# 06_SAMA7G54-MPU.net
KiCad netlist of a schematic drawn in Altium Designer
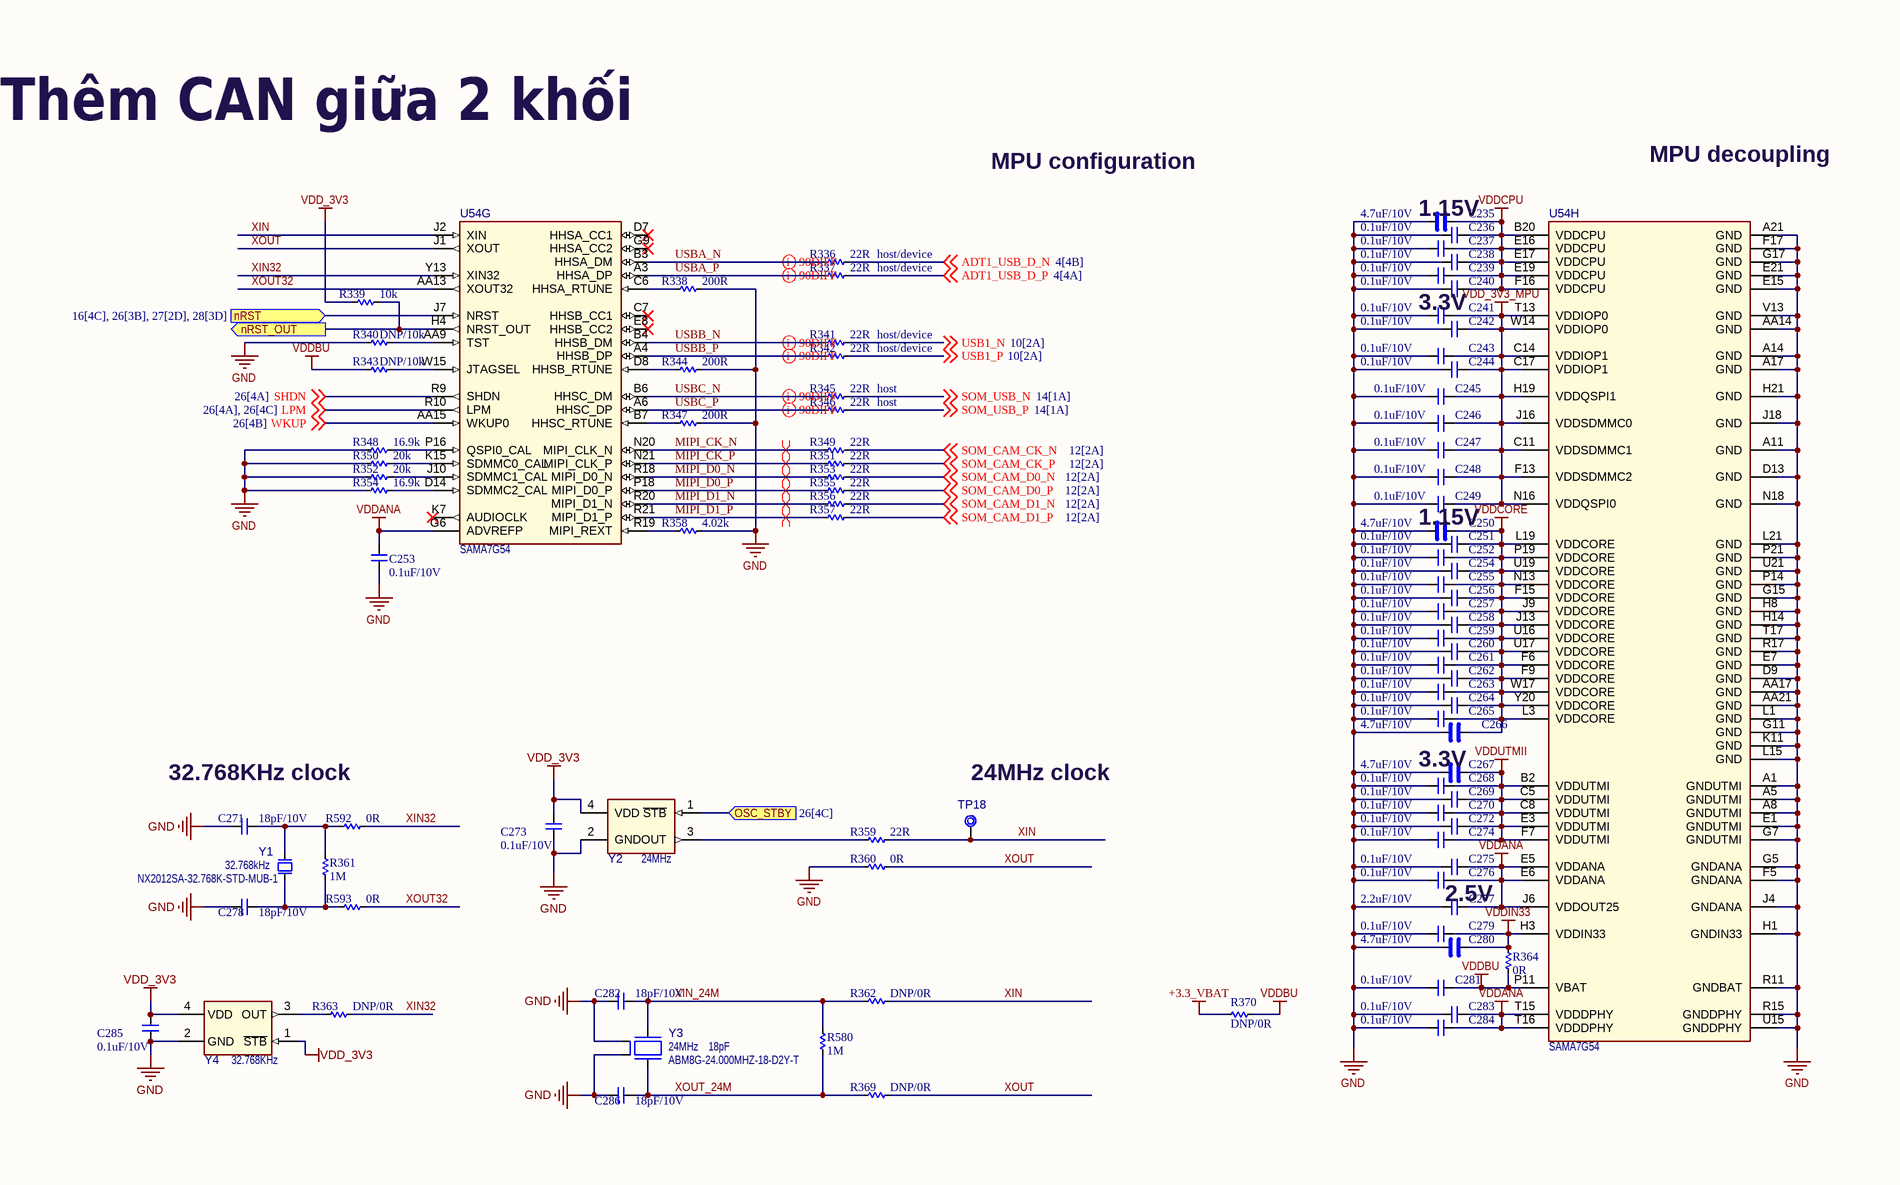
[diagram p0: 06_SAMA7G54-MPU.SchDoc, top left]
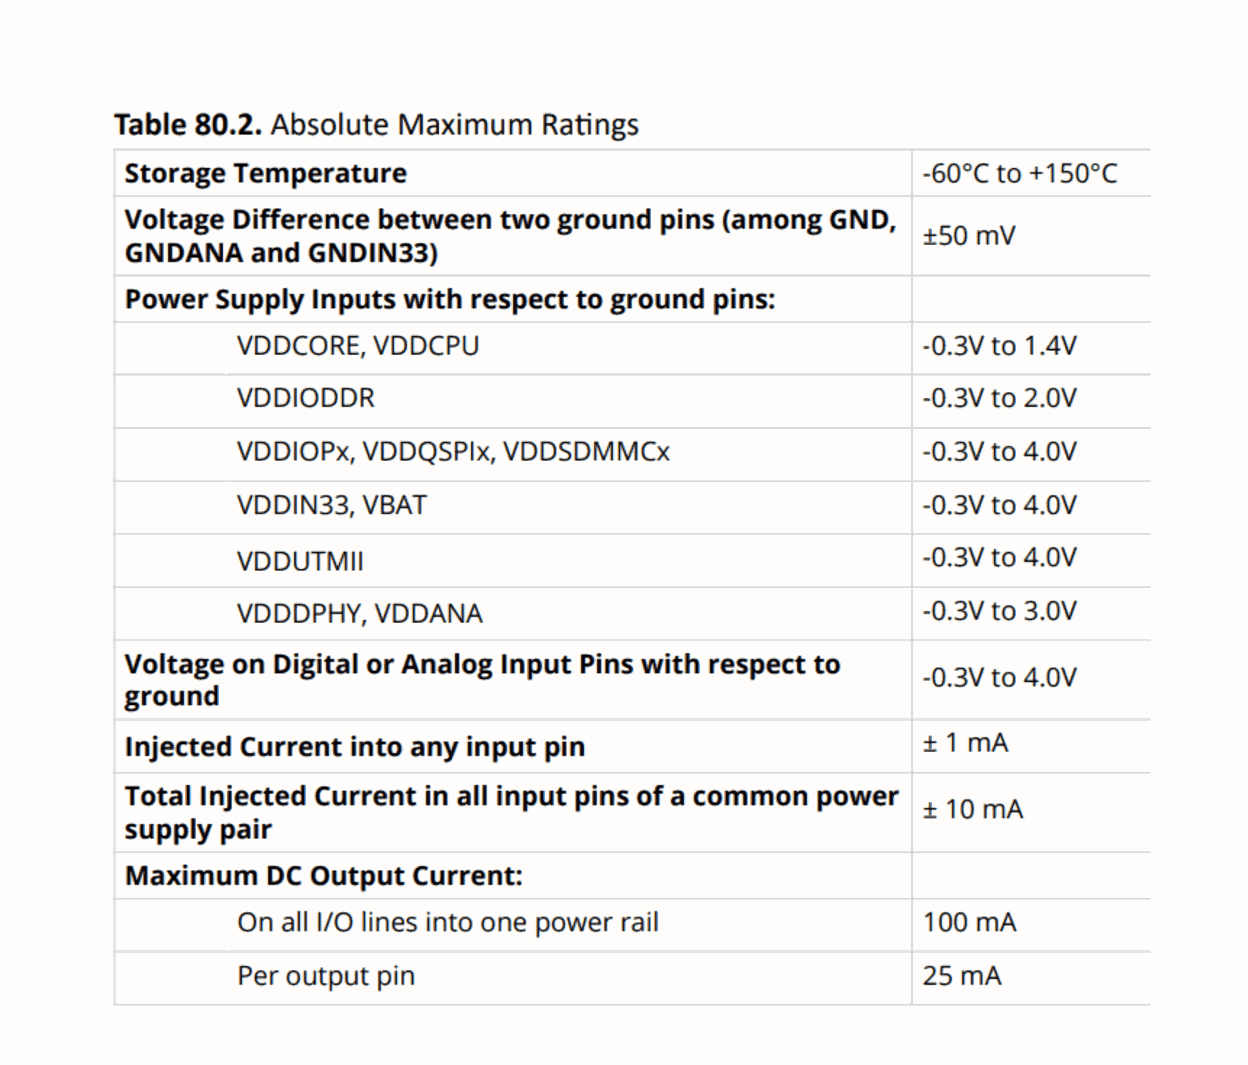
[diagram p1: 06_SAMA7G54-MPU.SchDoc, top right]
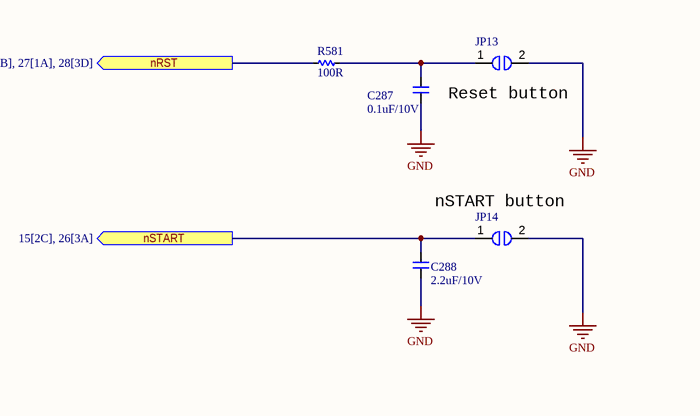
[diagram p2: 06_SAMA7G54-MPU.SchDoc, bottom left]
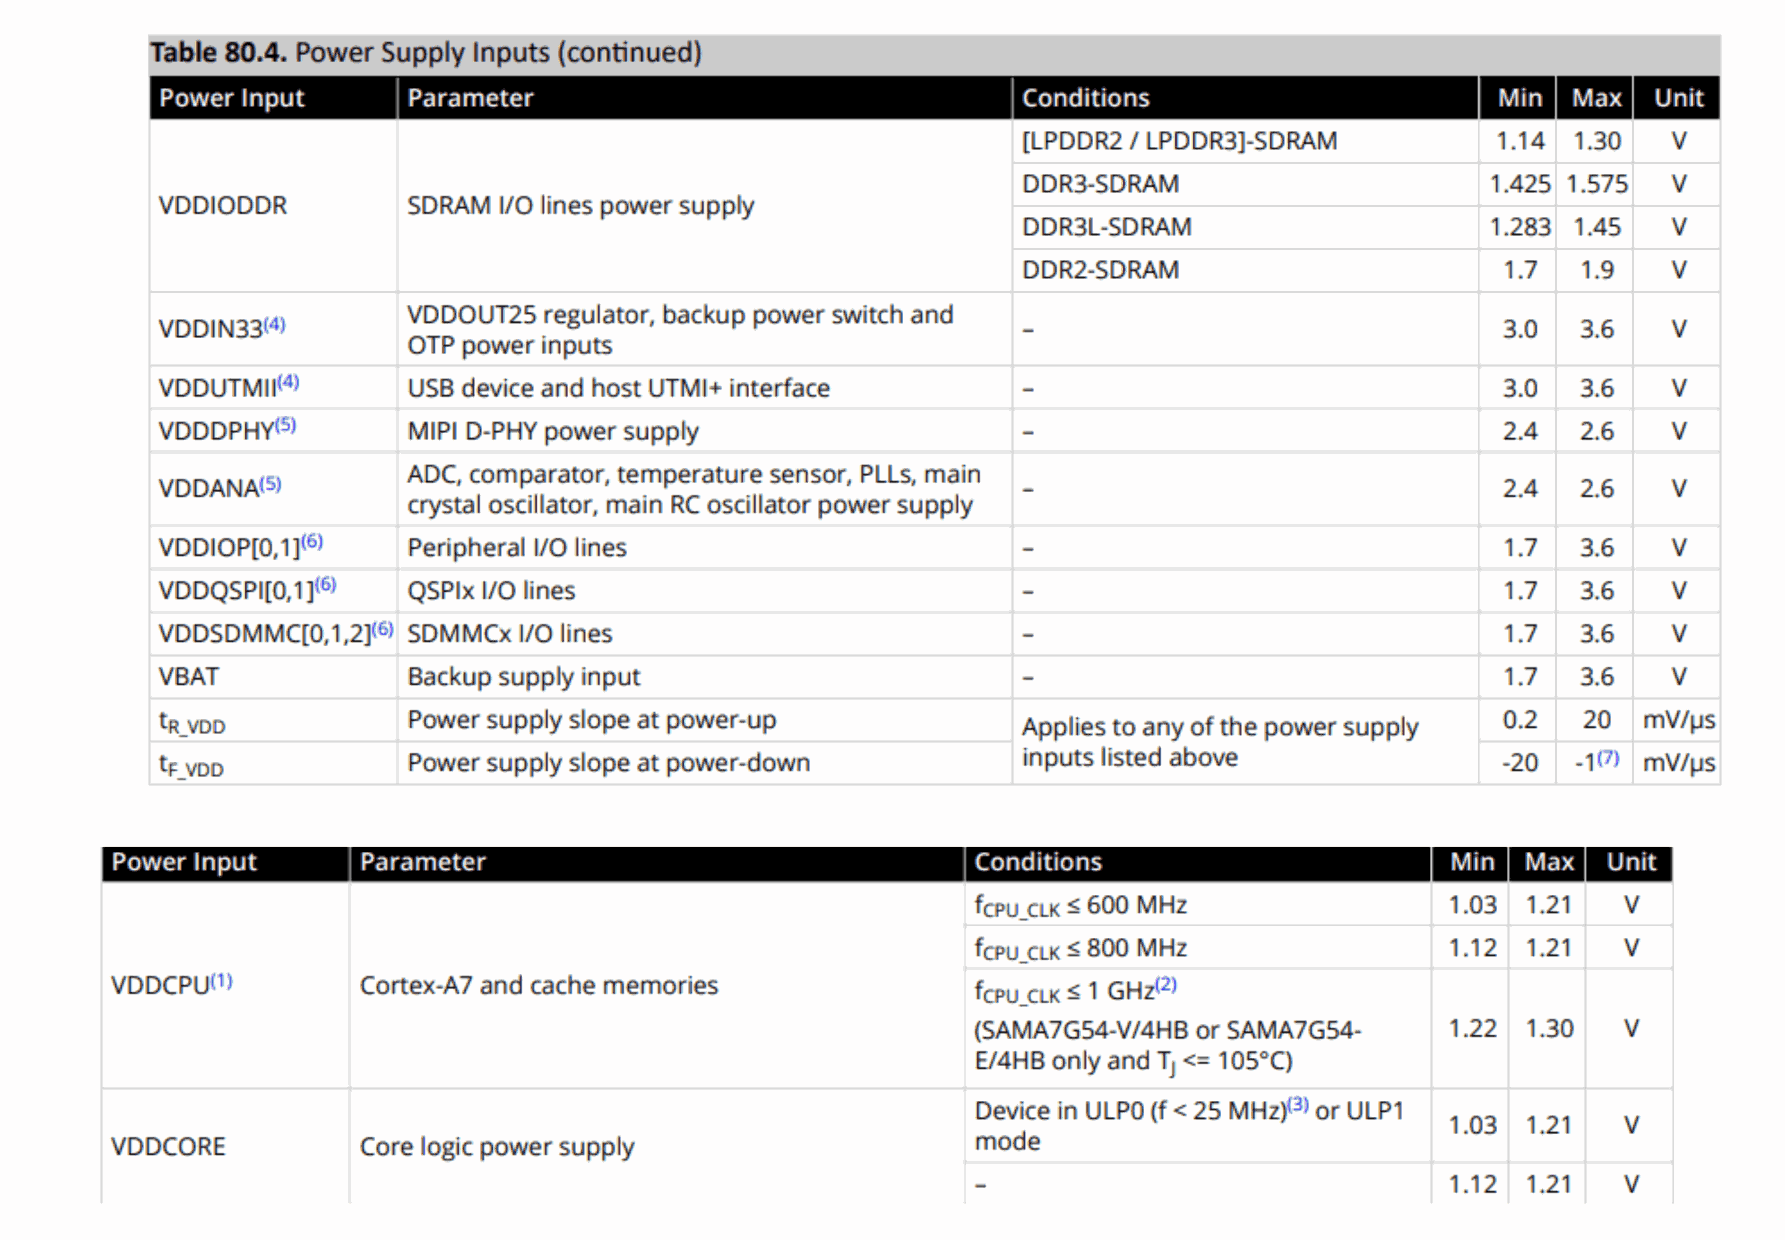
[diagram p3: 06_SAMA7G54-MPU.SchDoc, bottom right]

(export (version "E")
  (design (tool "Eeschema 10.0.6"))
  (components
    (comp (ref "C235")
      (value "4.7uF/10V")
      (footprint "CAP_C_1005X60")
      (description "CAP CHIP High Value")
      (libsource (lib "LABLIB") (part "_CAP_C_High_2"))
    )
    (comp (ref "C236")
      (value "0.1uF/10V")
      (footprint "CAP_C_0603x30")
      (description "CAP CHIP")
      (libsource (lib "LABLIB") (part "_CAP_C_2"))
    )
    (comp (ref "C237")
      (value "0.1uF/10V")
      (footprint "CAP_C_0603x30")
      (description "CAP CHIP")
      (libsource (lib "LABLIB") (part "_CAP_C_2"))
    )
    (comp (ref "C238")
      (value "0.1uF/10V")
      (footprint "CAP_C_0603x30")
      (description "CAP CHIP")
      (libsource (lib "LABLIB") (part "_CAP_C_2"))
    )
    (comp (ref "C239")
      (value "0.1uF/10V")
      (footprint "CAP_C_0603x30")
      (description "CAP CHIP")
      (libsource (lib "LABLIB") (part "_CAP_C_2"))
    )
    (comp (ref "C240")
      (value "0.1uF/10V")
      (footprint "CAP_C_0603x30")
      (description "CAP CHIP")
      (libsource (lib "LABLIB") (part "_CAP_C_2"))
    )
    (comp (ref "C241")
      (value "0.1uF/10V")
      (footprint "CAP_C_0603x30")
      (description "CAP CHIP")
      (libsource (lib "LABLIB") (part "_CAP_C_2"))
    )
    (comp (ref "C242")
      (value "0.1uF/10V")
      (footprint "CAP_C_0603x30")
      (description "CAP CHIP")
      (libsource (lib "LABLIB") (part "_CAP_C_2"))
    )
    (comp (ref "C243")
      (value "0.1uF/10V")
      (footprint "CAP_C_0603x30")
      (description "CAP CHIP")
      (libsource (lib "LABLIB") (part "_CAP_C_2"))
    )
    (comp (ref "C244")
      (value "0.1uF/10V")
      (footprint "CAP_C_0603x30")
      (description "CAP CHIP")
      (libsource (lib "LABLIB") (part "_CAP_C_2"))
    )
    (comp (ref "C245")
      (value "0.1uF/10V")
      (footprint "CAP_C_0603x30")
      (description "CAP CHIP")
      (libsource (lib "LABLIB") (part "_CAP_C_2"))
    )
    (comp (ref "C246")
      (value "0.1uF/10V")
      (footprint "CAP_C_0603x30")
      (description "CAP CHIP")
      (libsource (lib "LABLIB") (part "_CAP_C_2"))
    )
    (comp (ref "C247")
      (value "0.1uF/10V")
      (footprint "CAP_C_0603x30")
      (description "CAP CHIP")
      (libsource (lib "LABLIB") (part "_CAP_C_2"))
    )
    (comp (ref "C248")
      (value "0.1uF/10V")
      (footprint "CAP_C_0603x30")
      (description "CAP CHIP")
      (libsource (lib "LABLIB") (part "_CAP_C_2"))
    )
    (comp (ref "C249")
      (value "0.1uF/10V")
      (footprint "CAP_C_0603x30")
      (description "CAP CHIP")
      (libsource (lib "LABLIB") (part "_CAP_C_2"))
    )
    (comp (ref "C250")
      (value "4.7uF/10V")
      (footprint "CAP_C_1005X60")
      (description "CAP CHIP High Value")
      (libsource (lib "LABLIB") (part "_CAP_C_High_2"))
    )
    (comp (ref "C251")
      (value "0.1uF/10V")
      (footprint "CAP_C_0603x30")
      (description "CAP CHIP")
      (libsource (lib "LABLIB") (part "_CAP_C_2"))
    )
    (comp (ref "C252")
      (value "0.1uF/10V")
      (footprint "CAP_C_0603x30")
      (description "CAP CHIP")
      (libsource (lib "LABLIB") (part "_CAP_C_2"))
    )
    (comp (ref "C253")
      (value "0.1uF/10V")
      (footprint "CAP_C_0603x30")
      (description "CAP CHIP")
      (libsource (lib "LABLIB") (part "_CAP_C_2"))
    )
    (comp (ref "C254")
      (value "0.1uF/10V")
      (footprint "CAP_C_0603x30")
      (description "CAP CHIP")
      (libsource (lib "LABLIB") (part "_CAP_C_2"))
    )
    (comp (ref "C255")
      (value "0.1uF/10V")
      (footprint "CAP_C_0603x30")
      (description "CAP CHIP")
      (libsource (lib "LABLIB") (part "_CAP_C_2"))
    )
    (comp (ref "C256")
      (value "0.1uF/10V")
      (footprint "CAP_C_0603x30")
      (description "CAP CHIP")
      (libsource (lib "LABLIB") (part "_CAP_C_2"))
    )
    (comp (ref "C257")
      (value "0.1uF/10V")
      (footprint "CAP_C_0603x30")
      (description "CAP CHIP")
      (libsource (lib "LABLIB") (part "_CAP_C_2"))
    )
    (comp (ref "C258")
      (value "0.1uF/10V")
      (footprint "CAP_C_0603x30")
      (description "CAP CHIP")
      (libsource (lib "LABLIB") (part "_CAP_C_2"))
    )
    (comp (ref "C259")
      (value "0.1uF/10V")
      (footprint "CAP_C_0603x30")
      (description "CAP CHIP")
      (libsource (lib "LABLIB") (part "_CAP_C_2"))
    )
    (comp (ref "C260")
      (value "0.1uF/10V")
      (footprint "CAP_C_0603x30")
      (description "CAP CHIP")
      (libsource (lib "LABLIB") (part "_CAP_C_2"))
    )
    (comp (ref "C261")
      (value "0.1uF/10V")
      (footprint "CAP_C_0603x30")
      (description "CAP CHIP")
      (libsource (lib "LABLIB") (part "_CAP_C_2"))
    )
    (comp (ref "C262")
      (value "0.1uF/10V")
      (footprint "CAP_C_0603x30")
      (description "CAP CHIP")
      (libsource (lib "LABLIB") (part "_CAP_C_2"))
    )
    (comp (ref "C263")
      (value "0.1uF/10V")
      (footprint "CAP_C_0603x30")
      (description "CAP CHIP")
      (libsource (lib "LABLIB") (part "_CAP_C_2"))
    )
    (comp (ref "C264")
      (value "0.1uF/10V")
      (footprint "CAP_C_0603x30")
      (description "CAP CHIP")
      (libsource (lib "LABLIB") (part "_CAP_C_2"))
    )
    (comp (ref "C265")
      (value "0.1uF/10V")
      (footprint "CAP_C_0603x30")
      (description "CAP CHIP")
      (libsource (lib "LABLIB") (part "_CAP_C_2"))
    )
    (comp (ref "C266")
      (value "4.7uF/10V")
      (footprint "CAP_C_1005X60")
      (description "CAP CHIP High Value")
      (libsource (lib "LABLIB") (part "_CAP_C_High_2"))
    )
    (comp (ref "C267")
      (value "4.7uF/10V")
      (footprint "CAP_C_1005X60")
      (description "CAP CHIP High Value")
      (libsource (lib "LABLIB") (part "_CAP_C_High_2"))
    )
    (comp (ref "C268")
      (value "0.1uF/10V")
      (footprint "CAP_C_0603x30")
      (description "CAP CHIP")
      (libsource (lib "LABLIB") (part "_CAP_C_2"))
    )
    (comp (ref "C269")
      (value "0.1uF/10V")
      (footprint "CAP_C_0603x30")
      (description "CAP CHIP")
      (libsource (lib "LABLIB") (part "_CAP_C_2"))
    )
    (comp (ref "C270")
      (value "0.1uF/10V")
      (footprint "CAP_C_0603x30")
      (description "CAP CHIP")
      (libsource (lib "LABLIB") (part "_CAP_C_2"))
    )
    (comp (ref "C271")
      (value "18pF/10V")
      (footprint "CAP_C_1005X60")
      (description "CAP CHIP")
      (libsource (lib "LABLIB") (part "_CAP_C_2"))
    )
    (comp (ref "C272")
      (value "0.1uF/10V")
      (footprint "CAP_C_0603x30")
      (description "CAP CHIP")
      (libsource (lib "LABLIB") (part "_CAP_C_2"))
    )
    (comp (ref "C273")
      (value "0.1uF/10V")
      (footprint "CAP_C_1005X60")
      (description "CAP CHIP")
      (libsource (lib "LABLIB") (part "_CAP_C_2"))
    )
    (comp (ref "C274")
      (value "0.1uF/10V")
      (footprint "CAP_C_0603x30")
      (description "CAP CHIP")
      (libsource (lib "LABLIB") (part "_CAP_C_2"))
    )
    (comp (ref "C275")
      (value "0.1uF/10V")
      (footprint "CAP_C_0603x30")
      (description "CAP CHIP")
      (libsource (lib "LABLIB") (part "_CAP_C_2"))
    )
    (comp (ref "C276")
      (value "0.1uF/10V")
      (footprint "CAP_C_0603x30")
      (description "CAP CHIP")
      (libsource (lib "LABLIB") (part "_CAP_C_2"))
    )
    (comp (ref "C277")
      (value "2.2uF/10V")
      (footprint "CAP_C_1005X50_L")
      (description "CAP CHIP")
      (libsource (lib "LABLIB") (part "_CAP_C_2"))
    )
    (comp (ref "C278")
      (value "18pF/10V")
      (footprint "CAP_C_1005X60")
      (description "CAP CHIP")
      (libsource (lib "LABLIB") (part "_CAP_C_2"))
    )
    (comp (ref "C279")
      (value "0.1uF/10V")
      (footprint "CAP_C_0603x30")
      (description "CAP CHIP")
      (libsource (lib "LABLIB") (part "_CAP_C_2"))
    )
    (comp (ref "C280")
      (value "4.7uF/10V")
      (footprint "CAP_C_1005X60")
      (description "CAP CHIP High Value")
      (libsource (lib "LABLIB") (part "_CAP_C_High_2"))
    )
    (comp (ref "C281")
      (value "0.1uF/10V")
      (footprint "CAP_C_0603x30")
      (description "CAP CHIP")
      (libsource (lib "LABLIB") (part "_CAP_C_2"))
    )
    (comp (ref "C282")
      (value "18pF/10V")
      (footprint "CAP_C_1005X60")
      (description "CAP CHIP")
      (libsource (lib "LABLIB") (part "_CAP_C_2"))
    )
    (comp (ref "C283")
      (value "0.1uF/10V")
      (footprint "CAP_C_0603x30")
      (description "CAP CHIP")
      (libsource (lib "LABLIB") (part "_CAP_C_2"))
    )
    (comp (ref "C284")
      (value "0.1uF/10V")
      (footprint "CAP_C_0603x30")
      (description "CAP CHIP")
      (libsource (lib "LABLIB") (part "_CAP_C_2"))
    )
    (comp (ref "C285")
      (value "0.1uF/10V")
      (footprint "CAP_C_1005X60")
      (description "CAP CHIP")
      (libsource (lib "LABLIB") (part "_CAP_C_2"))
    )
    (comp (ref "C286")
      (value "18pF/10V")
      (footprint "CAP_C_1005X60")
      (description "CAP CHIP")
      (libsource (lib "LABLIB") (part "_CAP_C_2"))
    )
    (comp (ref "C287")
      (value "0.1uF/10V")
      (footprint "CAP_C_1005X60")
      (description "CAP CHIP")
      (libsource (lib "LABLIB") (part "_CAP_C_2"))
    )
    (comp (ref "C288")
      (value "2.2uF/10V")
      (footprint "CAP_C_1005X50_L")
      (description "CAP CHIP")
      (libsource (lib "LABLIB") (part "_CAP_C_2"))
    )
    (comp (ref "JP13")
      (value "~")
      (footprint "TESTPOINT_SHORT_120X100_60")
      (libsource (lib "LABLIB") (part "JUMPER_1_1"))
    )
    (comp (ref "JP14")
      (value "~")
      (footprint "TESTPOINT_SHORT_120X100_60")
      (libsource (lib "LABLIB") (part "JUMPER_1_1"))
    )
    (comp (ref "R336")
      (value "22R")
      (footprint "RES_C_0603X30")
      (description "RES")
      (libsource (lib "LABLIB") (part "_RES_B_2"))
    )
    (comp (ref "R337")
      (value "22R")
      (footprint "RES_C_0603X30")
      (description "RES")
      (libsource (lib "LABLIB") (part "_RES_B_2"))
    )
    (comp (ref "R338")
      (value "200R")
      (footprint "RES_C_0603X30")
      (description "RES")
      (libsource (lib "LABLIB") (part "_RES_B_2"))
    )
    (comp (ref "R339")
      (value "10k")
      (footprint "RES_C_1005X40")
      (description "RES")
      (libsource (lib "LABLIB") (part "_RES_B_2"))
    )
    (comp (ref "R340")
      (value "DNP/10k")
      (footprint "RES_C_1005X40")
      (description "RES")
      (libsource (lib "LABLIB") (part "_RES_B_2"))
    )
    (comp (ref "R341")
      (value "22R")
      (footprint "RES_C_0603X30")
      (description "RES")
      (libsource (lib "LABLIB") (part "_RES_B_2"))
    )
    (comp (ref "R342")
      (value "22R")
      (footprint "RES_C_0603X30")
      (description "RES")
      (libsource (lib "LABLIB") (part "_RES_B_2"))
    )
    (comp (ref "R343")
      (value "DNP/10k")
      (footprint "RES_C_1005X40")
      (description "RES")
      (libsource (lib "LABLIB") (part "_RES_B_2"))
    )
    (comp (ref "R344")
      (value "200R")
      (footprint "RES_C_0603X30")
      (description "RES")
      (libsource (lib "LABLIB") (part "_RES_B_2"))
    )
    (comp (ref "R345")
      (value "22R")
      (footprint "RES_C_0603X30")
      (description "RES")
      (libsource (lib "LABLIB") (part "_RES_B_2"))
    )
    (comp (ref "R346")
      (value "22R")
      (footprint "RES_C_0603X30")
      (description "RES")
      (libsource (lib "LABLIB") (part "_RES_B_2"))
    )
    (comp (ref "R347")
      (value "200R")
      (footprint "RES_C_0603X30")
      (description "RES")
      (libsource (lib "LABLIB") (part "_RES_B_2"))
    )
    (comp (ref "R348")
      (value "16.9k")
      (footprint "RES_C_0603X30")
      (description "RES")
      (libsource (lib "LABLIB") (part "_RES_B_2"))
    )
    (comp (ref "R349")
      (value "22R")
      (footprint "RES_C_0603X30")
      (description "RES")
      (libsource (lib "LABLIB") (part "_RES_B_2"))
    )
    (comp (ref "R350")
      (value "20k")
      (footprint "RES_C_0603X30")
      (description "RES")
      (libsource (lib "LABLIB") (part "_RES_B_2"))
    )
    (comp (ref "R351")
      (value "22R")
      (footprint "RES_C_0603X30")
      (description "RES")
      (libsource (lib "LABLIB") (part "_RES_B_2"))
    )
    (comp (ref "R352")
      (value "20k")
      (footprint "RES_C_0603X30")
      (description "RES")
      (libsource (lib "LABLIB") (part "_RES_B_2"))
    )
    (comp (ref "R353")
      (value "22R")
      (footprint "RES_C_0603X30")
      (description "RES")
      (libsource (lib "LABLIB") (part "_RES_B_2"))
    )
    (comp (ref "R354")
      (value "16.9k")
      (footprint "RES_C_0603X30")
      (description "RES")
      (libsource (lib "LABLIB") (part "_RES_B_2"))
    )
    (comp (ref "R355")
      (value "22R")
      (footprint "RES_C_0603X30")
      (description "RES")
      (libsource (lib "LABLIB") (part "_RES_B_2"))
    )
    (comp (ref "R356")
      (value "22R")
      (footprint "RES_C_0603X30")
      (description "RES")
      (libsource (lib "LABLIB") (part "_RES_B_2"))
    )
    (comp (ref "R357")
      (value "22R")
      (footprint "RES_C_0603X30")
      (description "RES")
      (libsource (lib "LABLIB") (part "_RES_B_2"))
    )
    (comp (ref "R358")
      (value "4.02k")
      (footprint "RES_C_0603X30")
      (description "RES")
      (libsource (lib "LABLIB") (part "_RES_B_2"))
    )
    (comp (ref "R359")
      (value "22R")
      (footprint "RES_C_1005X40")
      (description "RES")
      (libsource (lib "LABLIB") (part "_RES_B_2"))
    )
    (comp (ref "R360")
      (value "0R")
      (footprint "RES_C_1005X40")
      (description "RES")
      (libsource (lib "LABLIB") (part "_RES_B_2"))
    )
    (comp (ref "R361")
      (value "1M")
      (footprint "RES_C_1005X40")
      (description "RES")
      (libsource (lib "LABLIB") (part "_RES_B_2"))
    )
    (comp (ref "R362")
      (value "DNP/0R")
      (footprint "RES_C_1005X40")
      (description "RES")
      (libsource (lib "LABLIB") (part "_RES_B_2"))
    )
    (comp (ref "R363")
      (value "DNP/0R")
      (footprint "RES_C_1005X40")
      (description "RES")
      (libsource (lib "LABLIB") (part "_RES_B_2"))
    )
    (comp (ref "R364")
      (value "0R")
      (footprint "RES_C_1005X40")
      (description "RES")
      (libsource (lib "LABLIB") (part "_RES_B_2"))
    )
    (comp (ref "R369")
      (value "DNP/0R")
      (footprint "RES_C_1005X40")
      (description "RES")
      (libsource (lib "LABLIB") (part "_RES_B_2"))
    )
    (comp (ref "R370")
      (value "DNP/0R")
      (footprint "RES_C_1005X40")
      (description "RES")
      (libsource (lib "LABLIB") (part "_RES_B_2"))
    )
    (comp (ref "R580")
      (value "1M")
      (footprint "RES_C_1005X40")
      (description "RES")
      (libsource (lib "LABLIB") (part "_RES_B_2"))
    )
    (comp (ref "R581")
      (value "100R")
      (footprint "RES_C_1005X40")
      (description "RES")
      (libsource (lib "LABLIB") (part "_RES_B_2"))
    )
    (comp (ref "R592")
      (value "0R")
      (footprint "RES_C_1005X40")
      (description "RES")
      (libsource (lib "LABLIB") (part "_RES_B_2"))
    )
    (comp (ref "R593")
      (value "0R")
      (footprint "RES_C_1005X40")
      (description "RES")
      (libsource (lib "LABLIB") (part "_RES_B_2"))
    )
    (comp (ref "TP18")
      (value "Test Point No BOM")
      (footprint "Testpoint_80")
      (description "Test Point")
      (fields (field (name "OWNER") "Cristian Papuc"))
      (libsource (lib "MCHP-CDB") (part "Test Point No BOM"))
    )
    (comp (ref "U54")
      (value "SAMA7G54")
      (footprint "TFBGA-343_14x14")
      (description "SAMA7G54 MPU 1000MHz Cortex-A7 TFBGA-343")
      (fields (field (name "OWNER") "Ciprian Abramov"))
      (libsource (lib "MCHP-CDB") (part "SAMA7G54 TFBGA-343"))
    )
    (comp (ref "Y1")
      (value "32.768kHz")
      (footprint "CRYSTAL_NX2012SA")
      (description "Crystal")
      (fields
        (field (name "TOLERANCE") "±20ppm")
        (field (name "MANUFACTURER PART NUMBER 1") "NX2012SA-32.768K-STD-MUB-1")
        (field (name "Comment") "Crystal 2 Pins")
        (field (name "OWNER") "Jamus Griego")
      )
      (libsource (lib "MCHP-CDB") (part "Crystal 2 Pins"))
    )
    (comp (ref "Y2")
      (value "24MHz")
      (footprint "DFN-4_2.5x2")
      (fields (field (name "Comment") "DSC10xx DFN-4") (field (name "OWNER") "Maurizio Gavardoni"))
      (libsource (lib "MCHP-CDB") (part "DSC10xx DFN-4"))
    )
    (comp (ref "Y3")
      (value "24MHz")
      (footprint "CRYSTAL_ABM8G")
      (description "Crystal")
      (fields
        (field (name "LOAD CAPACITANCE") "18pF")
        (field (name "MANUFACTURER PART NUMBER 1") "ABM8G-24.000MHZ-18-D2Y-T")
        (field (name "Comment") "Crystal 4 Pins")
        (field (name "OWNER") "Mark Loper")
      )
      (libsource (lib "MCHP-CDB") (part "Crystal 4 Pins"))
    )
    (comp (ref "Y4")
      (value "32.768KHz")
      (footprint "DFN-4_2x1.6")
      (fields (field (name "Comment") "DSC60xx DFN-4_LGA-4") (field (name "OWNER") "Ciprian Abramov"))
      (libsource (lib "MCHP-CDB") (part "DSC60xx DFN-4_LGA-4"))
    )
  )
  (nets
    (net (code "1") (name "+3.3_VBAT") (class "Default")
      (node (ref "R370") (pin "1") (pinfunction "1_1") (pintype "passive"))
    )
    (net (code "2") (name "/MIPI_CK_N") (class "Default")
      (node (ref "R349") (pin "2") (pinfunction "2_2") (pintype "passive"))
      (node (ref "U54") (pin "N20") (pinfunction "MIPI_CLK_N_N20") (pintype "bidirectional"))
    )
    (net (code "3") (name "/MIPI_CK_P") (class "Default")
      (node (ref "R351") (pin "2") (pinfunction "2_2") (pintype "passive"))
      (node (ref "U54") (pin "N21") (pinfunction "MIPI_CLK_P_N21") (pintype "bidirectional"))
    )
    (net (code "4") (name "/MIPI_D0_N") (class "Default")
      (node (ref "R353") (pin "2") (pinfunction "2_2") (pintype "passive"))
      (node (ref "U54") (pin "R18") (pinfunction "MIPI_D0_N_R18") (pintype "bidirectional"))
    )
    (net (code "5") (name "/MIPI_D0_P") (class "Default")
      (node (ref "R355") (pin "2") (pinfunction "2_2") (pintype "passive"))
      (node (ref "U54") (pin "P18") (pinfunction "MIPI_D0_P_P18") (pintype "bidirectional"))
    )
    (net (code "6") (name "/MIPI_D1_N") (class "Default")
      (node (ref "R356") (pin "2") (pinfunction "2_2") (pintype "passive"))
      (node (ref "U54") (pin "R20") (pinfunction "MIPI_D1_N_R20") (pintype "bidirectional"))
    )
    (net (code "7") (name "/MIPI_D1_P") (class "Default")
      (node (ref "R357") (pin "2") (pinfunction "2_2") (pintype "passive"))
      (node (ref "U54") (pin "R21") (pinfunction "MIPI_D1_P_R21") (pintype "bidirectional"))
    )
    (net (code "8") (name "/OSC_STBY") (class "Default")
      (node (ref "Y2") (pin "1") (pinfunction "~{STB}_1") (pintype "input"))
    )
    (net (code "9") (name "/USBA_N") (class "Default")
      (node (ref "R336") (pin "2") (pinfunction "2_2") (pintype "passive"))
      (node (ref "U54") (pin "B3") (pinfunction "HHSA_DM_B3") (pintype "bidirectional"))
    )
    (net (code "10") (name "/USBA_P") (class "Default")
      (node (ref "R337") (pin "2") (pinfunction "2_2") (pintype "passive"))
      (node (ref "U54") (pin "A3") (pinfunction "HHSA_DP_A3") (pintype "bidirectional"))
    )
    (net (code "11") (name "/USBB_N") (class "Default")
      (node (ref "R341") (pin "2") (pinfunction "2_2") (pintype "passive"))
      (node (ref "U54") (pin "B4") (pinfunction "HHSB_DM_B4") (pintype "bidirectional"))
    )
    (net (code "12") (name "/USBB_P") (class "Default")
      (node (ref "R342") (pin "2") (pinfunction "2_2") (pintype "passive"))
      (node (ref "U54") (pin "A4") (pinfunction "HHSB_DP_A4") (pintype "bidirectional"))
    )
    (net (code "13") (name "/USBC_N") (class "Default")
      (node (ref "R345") (pin "2") (pinfunction "2_2") (pintype "passive"))
      (node (ref "U54") (pin "B6") (pinfunction "HHSC_DM_B6") (pintype "bidirectional"))
    )
    (net (code "14") (name "/USBC_P") (class "Default")
      (node (ref "R346") (pin "2") (pinfunction "2_2") (pintype "passive"))
      (node (ref "U54") (pin "A6") (pinfunction "HHSC_DP_A6") (pintype "bidirectional"))
    )
    (net (code "15") (name "/XIN") (class "Default")
      (node (ref "R359") (pin "2") (pinfunction "2_2") (pintype "passive"))
      (node (ref "R362") (pin "2") (pinfunction "2_2") (pintype "passive"))
      (node (ref "TP18") (pin "1") (pinfunction "1_1") (pintype "passive"))
      (node (ref "U54") (pin "J2") (pinfunction "XIN_J2") (pintype "input"))
    )
    (net (code "16") (name "/XIN32") (class "Default")
      (node (ref "R363") (pin "2") (pinfunction "2_2") (pintype "passive"))
      (node (ref "R592") (pin "2") (pinfunction "2_2") (pintype "passive"))
      (node (ref "U54") (pin "Y13") (pinfunction "XIN32_Y13") (pintype "input"))
    )
    (net (code "17") (name "/XIN_24M") (class "Default")
      (node (ref "C282") (pin "1") (pinfunction "1_1") (pintype "passive"))
      (node (ref "R362") (pin "1") (pinfunction "1_1") (pintype "passive"))
      (node (ref "R580") (pin "1") (pinfunction "1_1") (pintype "passive"))
      (node (ref "Y3") (pin "3") (pinfunction "Osc2_3") (pintype "passive"))
    )
    (net (code "18") (name "/XOUT") (class "Default")
      (node (ref "R360") (pin "2") (pinfunction "2_2") (pintype "passive"))
      (node (ref "R369") (pin "2") (pinfunction "2_2") (pintype "passive"))
      (node (ref "U54") (pin "J1") (pinfunction "XOUT_J1") (pintype "output"))
    )
    (net (code "19") (name "/XOUT32") (class "Default")
      (node (ref "R593") (pin "2") (pinfunction "2_2") (pintype "passive"))
      (node (ref "U54") (pin "AA13") (pinfunction "XOUT32_AA13") (pintype "output"))
    )
    (net (code "20") (name "/XOUT_24M") (class "Default")
      (node (ref "C286") (pin "1") (pinfunction "1_1") (pintype "passive"))
      (node (ref "R369") (pin "1") (pinfunction "1_1") (pintype "passive"))
      (node (ref "R580") (pin "2") (pinfunction "2_2") (pintype "passive"))
      (node (ref "Y3") (pin "1") (pinfunction "Osc1_1") (pintype "passive"))
    )
    (net (code "21") (name "/nRST") (class "Default")
      (node (ref "R581") (pin "1") (pinfunction "1_1") (pintype "passive"))
      (node (ref "U54") (pin "J7") (pinfunction "NRST_J7") (pintype "input"))
    )
    (net (code "22") (name "/nRST_OUT") (class "Default")
      (node (ref "R339") (pin "1") (pinfunction "1_1") (pintype "passive"))
      (node (ref "U54") (pin "H4") (pinfunction "NRST_OUT_H4") (pintype "output"))
    )
    (net (code "23") (name "/nSTART") (class "Default")
      (node (ref "C288") (pin "1") (pinfunction "1_1") (pintype "passive"))
      (node (ref "JP14") (pin "1") (pinfunction "1_1") (pintype "passive"))
    )
    (net (code "24") (name "ADT1_USB_D_N") (class "Default")
      (node (ref "R336") (pin "1") (pinfunction "1_1") (pintype "passive"))
    )
    (net (code "25") (name "ADT1_USB_D_P") (class "Default")
      (node (ref "R337") (pin "1") (pinfunction "1_1") (pintype "passive"))
    )
    (net (code "26") (name "GND") (class "Default")
      (node (ref "C235") (pin "2") (pinfunction "2_2") (pintype "passive"))
      (node (ref "C236") (pin "2") (pinfunction "2_2") (pintype "passive"))
      (node (ref "C237") (pin "2") (pinfunction "2_2") (pintype "passive"))
      (node (ref "C238") (pin "2") (pinfunction "2_2") (pintype "passive"))
      (node (ref "C239") (pin "2") (pinfunction "2_2") (pintype "passive"))
      (node (ref "C240") (pin "2") (pinfunction "2_2") (pintype "passive"))
      (node (ref "C241") (pin "2") (pinfunction "2_2") (pintype "passive"))
      (node (ref "C242") (pin "2") (pinfunction "2_2") (pintype "passive"))
      (node (ref "C243") (pin "2") (pinfunction "2_2") (pintype "passive"))
      (node (ref "C244") (pin "2") (pinfunction "2_2") (pintype "passive"))
      (node (ref "C245") (pin "2") (pinfunction "2_2") (pintype "passive"))
      (node (ref "C246") (pin "2") (pinfunction "2_2") (pintype "passive"))
      (node (ref "C247") (pin "2") (pinfunction "2_2") (pintype "passive"))
      (node (ref "C248") (pin "2") (pinfunction "2_2") (pintype "passive"))
      (node (ref "C249") (pin "2") (pinfunction "2_2") (pintype "passive"))
      (node (ref "C250") (pin "2") (pinfunction "2_2") (pintype "passive"))
      (node (ref "C251") (pin "2") (pinfunction "2_2") (pintype "passive"))
      (node (ref "C252") (pin "2") (pinfunction "2_2") (pintype "passive"))
      (node (ref "C253") (pin "1") (pinfunction "1_1") (pintype "passive"))
      (node (ref "C254") (pin "2") (pinfunction "2_2") (pintype "passive"))
      (node (ref "C255") (pin "2") (pinfunction "2_2") (pintype "passive"))
      (node (ref "C256") (pin "2") (pinfunction "2_2") (pintype "passive"))
      (node (ref "C257") (pin "2") (pinfunction "2_2") (pintype "passive"))
      (node (ref "C258") (pin "2") (pinfunction "2_2") (pintype "passive"))
      (node (ref "C259") (pin "2") (pinfunction "2_2") (pintype "passive"))
      (node (ref "C260") (pin "2") (pinfunction "2_2") (pintype "passive"))
      (node (ref "C261") (pin "2") (pinfunction "2_2") (pintype "passive"))
      (node (ref "C262") (pin "2") (pinfunction "2_2") (pintype "passive"))
      (node (ref "C263") (pin "2") (pinfunction "2_2") (pintype "passive"))
      (node (ref "C264") (pin "2") (pinfunction "2_2") (pintype "passive"))
      (node (ref "C265") (pin "2") (pinfunction "2_2") (pintype "passive"))
      (node (ref "C266") (pin "2") (pinfunction "2_2") (pintype "passive"))
      (node (ref "C267") (pin "2") (pinfunction "2_2") (pintype "passive"))
      (node (ref "C268") (pin "2") (pinfunction "2_2") (pintype "passive"))
      (node (ref "C269") (pin "2") (pinfunction "2_2") (pintype "passive"))
      (node (ref "C270") (pin "2") (pinfunction "2_2") (pintype "passive"))
      (node (ref "C271") (pin "2") (pinfunction "2_2") (pintype "passive"))
      (node (ref "C272") (pin "2") (pinfunction "2_2") (pintype "passive"))
      (node (ref "C273") (pin "1") (pinfunction "1_1") (pintype "passive"))
      (node (ref "C274") (pin "2") (pinfunction "2_2") (pintype "passive"))
      (node (ref "C275") (pin "2") (pinfunction "2_2") (pintype "passive"))
      (node (ref "C276") (pin "2") (pinfunction "2_2") (pintype "passive"))
      (node (ref "C277") (pin "2") (pinfunction "2_2") (pintype "passive"))
      (node (ref "C278") (pin "2") (pinfunction "2_2") (pintype "passive"))
      (node (ref "C279") (pin "2") (pinfunction "2_2") (pintype "passive"))
      (node (ref "C280") (pin "2") (pinfunction "2_2") (pintype "passive"))
      (node (ref "C281") (pin "2") (pinfunction "2_2") (pintype "passive"))
      (node (ref "C282") (pin "2") (pinfunction "2_2") (pintype "passive"))
      (node (ref "C283") (pin "2") (pinfunction "2_2") (pintype "passive"))
      (node (ref "C284") (pin "2") (pinfunction "2_2") (pintype "passive"))
      (node (ref "C285") (pin "1") (pinfunction "1_1") (pintype "passive"))
      (node (ref "C286") (pin "2") (pinfunction "2_2") (pintype "passive"))
      (node (ref "C287") (pin "1") (pinfunction "1_1") (pintype "passive"))
      (node (ref "C288") (pin "2") (pinfunction "2_2") (pintype "passive"))
      (node (ref "JP13") (pin "2") (pinfunction "2_2") (pintype "passive"))
      (node (ref "JP14") (pin "2") (pinfunction "2_2") (pintype "passive"))
      (node (ref "R338") (pin "1") (pinfunction "1_1") (pintype "passive"))
      (node (ref "R340") (pin "2") (pinfunction "2_2") (pintype "passive"))
      (node (ref "R344") (pin "1") (pinfunction "1_1") (pintype "passive"))
      (node (ref "R347") (pin "1") (pinfunction "1_1") (pintype "passive"))
      (node (ref "R348") (pin "2") (pinfunction "2_2") (pintype "passive"))
      (node (ref "R350") (pin "2") (pinfunction "2_2") (pintype "passive"))
      (node (ref "R352") (pin "2") (pinfunction "2_2") (pintype "passive"))
      (node (ref "R354") (pin "2") (pinfunction "2_2") (pintype "passive"))
      (node (ref "R358") (pin "1") (pinfunction "1_1") (pintype "passive"))
      (node (ref "R360") (pin "1") (pinfunction "1_1") (pintype "passive"))
      (node (ref "U54") (pin "A1") (pinfunction "GNDUTMI_A1") (pintype "power_in"))
      (node (ref "U54") (pin "A11") (pinfunction "GND_A11") (pintype "power_in"))
      (node (ref "U54") (pin "A14") (pinfunction "GND_A14") (pintype "power_in"))
      (node (ref "U54") (pin "A17") (pinfunction "GND_A17") (pintype "power_in"))
      (node (ref "U54") (pin "A21") (pinfunction "GND_A21") (pintype "power_in"))
      (node (ref "U54") (pin "A5") (pinfunction "GNDUTMI_A5") (pintype "power_in"))
      (node (ref "U54") (pin "A8") (pinfunction "GNDUTMI_A8") (pintype "power_in"))
      (node (ref "U54") (pin "AA14") (pinfunction "GND_AA14") (pintype "power_in"))
      (node (ref "U54") (pin "AA17") (pinfunction "GND_AA17") (pintype "power_in"))
      (node (ref "U54") (pin "AA21") (pinfunction "GND_AA21") (pintype "power_in"))
      (node (ref "U54") (pin "D13") (pinfunction "GND_D13") (pintype "power_in"))
      (node (ref "U54") (pin "D9") (pinfunction "GND_D9") (pintype "power_in"))
      (node (ref "U54") (pin "E1") (pinfunction "GNDUTMI_E1") (pintype "power_in"))
      (node (ref "U54") (pin "E15") (pinfunction "GND_E15") (pintype "power_in"))
      (node (ref "U54") (pin "E21") (pinfunction "GND_E21") (pintype "power_in"))
      (node (ref "U54") (pin "E7") (pinfunction "GND_E7") (pintype "power_in"))
      (node (ref "U54") (pin "F17") (pinfunction "GND_F17") (pintype "power_in"))
      (node (ref "U54") (pin "F5") (pinfunction "GNDANA_F5") (pintype "power_in"))
      (node (ref "U54") (pin "G11") (pinfunction "GND_G11") (pintype "power_in"))
      (node (ref "U54") (pin "G15") (pinfunction "GND_G15") (pintype "power_in"))
      (node (ref "U54") (pin "G17") (pinfunction "GND_G17") (pintype "power_in"))
      (node (ref "U54") (pin "G5") (pinfunction "GNDANA_G5") (pintype "power_in"))
      (node (ref "U54") (pin "G7") (pinfunction "GNDUTMI_G7") (pintype "power_in"))
      (node (ref "U54") (pin "H1") (pinfunction "GNDIN33_H1") (pintype "power_in"))
      (node (ref "U54") (pin "H14") (pinfunction "GND_H14") (pintype "power_in"))
      (node (ref "U54") (pin "H21") (pinfunction "GND_H21") (pintype "power_in"))
      (node (ref "U54") (pin "H8") (pinfunction "GND_H8") (pintype "power_in"))
      (node (ref "U54") (pin "J18") (pinfunction "GND_J18") (pintype "power_in"))
      (node (ref "U54") (pin "J4") (pinfunction "GNDANAOUT_J4") (pintype "power_in"))
      (node (ref "U54") (pin "K11") (pinfunction "GND_K11") (pintype "power_in"))
      (node (ref "U54") (pin "L1") (pinfunction "GND_L1") (pintype "power_in"))
      (node (ref "U54") (pin "L15") (pinfunction "GND_L15") (pintype "power_in"))
      (node (ref "U54") (pin "L21") (pinfunction "GND_L21") (pintype "power_in"))
      (node (ref "U54") (pin "N18") (pinfunction "GND_N18") (pintype "power_in"))
      (node (ref "U54") (pin "P14") (pinfunction "GND_P14") (pintype "power_in"))
      (node (ref "U54") (pin "P21") (pinfunction "GND_P21") (pintype "power_in"))
      (node (ref "U54") (pin "R11") (pinfunction "GNDBAT_R11") (pintype "power_in"))
      (node (ref "U54") (pin "R15") (pinfunction "GNDDPHY_R15") (pintype "power_in"))
      (node (ref "U54") (pin "R17") (pinfunction "GND_R17") (pintype "power_in"))
      (node (ref "U54") (pin "T17") (pinfunction "GND_T17") (pintype "power_in"))
      (node (ref "U54") (pin "U15") (pinfunction "GNDDPHY_U15") (pintype "power_in"))
      (node (ref "U54") (pin "U21") (pinfunction "GND_U21") (pintype "power_in"))
      (node (ref "U54") (pin "V13") (pinfunction "GND_V13") (pintype "power_in"))
      (node (ref "Y2") (pin "2") (pinfunction "GND_2") (pintype "power_in"))
      (node (ref "Y3") (pin "2") (pinfunction "GND_2") (pintype "power_in"))
      (node (ref "Y3") (pin "4") (pinfunction "GND_4") (pintype "power_in"))
      (node (ref "Y4") (pin "2") (pinfunction "GND_2") (pintype "power_in"))
    )
    (net (code "27") (name "LPM") (class "Default")
      (node (ref "U54") (pin "R10") (pinfunction "LPM_R10") (pintype "output"))
    )
    (net (code "28") (name "Net-(C287-Pad2)") (class "Default")
      (node (ref "C287") (pin "2") (pinfunction "2_2") (pintype "passive"))
      (node (ref "JP13") (pin "1") (pinfunction "1_1") (pintype "passive"))
      (node (ref "R581") (pin "2") (pinfunction "2_2") (pintype "passive"))
    )
    (net (code "29") (name "Net-(U54G-HHSA_RTUNE)") (class "Default")
      (node (ref "R338") (pin "2") (pinfunction "2_2") (pintype "passive"))
      (node (ref "U54") (pin "C6") (pinfunction "HHSA_RTUNE_C6") (pintype "input"))
    )
    (net (code "30") (name "Net-(U54G-HHSB_RTUNE)") (class "Default")
      (node (ref "R344") (pin "2") (pinfunction "2_2") (pintype "passive"))
      (node (ref "U54") (pin "D8") (pinfunction "HHSB_RTUNE_D8") (pintype "input"))
    )
    (net (code "31") (name "Net-(U54G-HHSC_RTUNE)") (class "Default")
      (node (ref "R347") (pin "2") (pinfunction "2_2") (pintype "passive"))
      (node (ref "U54") (pin "B7") (pinfunction "HHSC_RTUNE_B7") (pintype "input"))
    )
    (net (code "32") (name "Net-(U54G-JTAGSEL)") (class "Default")
      (node (ref "R343") (pin "1") (pinfunction "1_1") (pintype "passive"))
      (node (ref "U54") (pin "W15") (pinfunction "JTAGSEL_W15") (pintype "input"))
    )
    (net (code "33") (name "Net-(U54G-MIPI_REXT)") (class "Default")
      (node (ref "R358") (pin "2") (pinfunction "2_2") (pintype "passive"))
      (node (ref "U54") (pin "R19") (pinfunction "MIPI_REXT_R19") (pintype "input"))
    )
    (net (code "34") (name "Net-(U54G-QSPI0_CAL)") (class "Default")
      (node (ref "R348") (pin "1") (pinfunction "1_1") (pintype "passive"))
      (node (ref "U54") (pin "P16") (pinfunction "QSPI0_CAL_P16") (pintype "input"))
    )
    (net (code "35") (name "Net-(U54G-SDMMC0_CAL)") (class "Default")
      (node (ref "R350") (pin "1") (pinfunction "1_1") (pintype "passive"))
      (node (ref "U54") (pin "K15") (pinfunction "SDMMC0_CAL_K15") (pintype "input"))
    )
    (net (code "36") (name "Net-(U54G-SDMMC1_CAL)") (class "Default")
      (node (ref "R352") (pin "1") (pinfunction "1_1") (pintype "passive"))
      (node (ref "U54") (pin "J10") (pinfunction "SDMMC1_CAL_J10") (pintype "input"))
    )
    (net (code "37") (name "Net-(U54G-SDMMC2_CAL)") (class "Default")
      (node (ref "R354") (pin "1") (pinfunction "1_1") (pintype "passive"))
      (node (ref "U54") (pin "D14") (pinfunction "SDMMC2_CAL_D14") (pintype "input"))
    )
    (net (code "38") (name "Net-(U54G-TST)") (class "Default")
      (node (ref "R340") (pin "1") (pinfunction "1_1") (pintype "passive"))
      (node (ref "U54") (pin "AA9") (pinfunction "TST_AA9") (pintype "input"))
    )
    (net (code "39") (name "Net-(Y1-Osc1)") (class "Default")
      (node (ref "C278") (pin "1") (pinfunction "1_1") (pintype "passive"))
      (node (ref "R361") (pin "2") (pinfunction "2_2") (pintype "passive"))
      (node (ref "R593") (pin "1") (pinfunction "1_1") (pintype "passive"))
      (node (ref "Y1") (pin "1") (pinfunction "Osc1_1") (pintype "passive"))
    )
    (net (code "40") (name "Net-(Y1-Osc2)") (class "Default")
      (node (ref "C271") (pin "1") (pinfunction "1_1") (pintype "passive"))
      (node (ref "R361") (pin "1") (pinfunction "1_1") (pintype "passive"))
      (node (ref "R592") (pin "1") (pinfunction "1_1") (pintype "passive"))
      (node (ref "Y1") (pin "2") (pinfunction "Osc2_2") (pintype "passive"))
    )
    (net (code "41") (name "Net-(Y2-OUT)") (class "Default")
      (node (ref "R359") (pin "1") (pinfunction "1_1") (pintype "passive"))
      (node (ref "Y2") (pin "3") (pinfunction "OUT_3") (pintype "output"))
    )
    (net (code "42") (name "Net-(Y4-OUT)") (class "Default")
      (node (ref "R363") (pin "1") (pinfunction "1_1") (pintype "passive"))
      (node (ref "Y4") (pin "3") (pinfunction "OUT_3") (pintype "output"))
    )
    (net (code "43") (name "SHDN") (class "Default")
      (node (ref "U54") (pin "R9") (pinfunction "SHDN_R9") (pintype "output"))
    )
    (net (code "44") (name "SOM_CAM_CK_N") (class "Default")
      (node (ref "R349") (pin "1") (pinfunction "1_1") (pintype "passive"))
    )
    (net (code "45") (name "SOM_CAM_CK_P") (class "Default")
      (node (ref "R351") (pin "1") (pinfunction "1_1") (pintype "passive"))
    )
    (net (code "46") (name "SOM_CAM_D0_N") (class "Default")
      (node (ref "R353") (pin "1") (pinfunction "1_1") (pintype "passive"))
    )
    (net (code "47") (name "SOM_CAM_D0_P") (class "Default")
      (node (ref "R355") (pin "1") (pinfunction "1_1") (pintype "passive"))
    )
    (net (code "48") (name "SOM_CAM_D1_N") (class "Default")
      (node (ref "R356") (pin "1") (pinfunction "1_1") (pintype "passive"))
    )
    (net (code "49") (name "SOM_CAM_D1_P") (class "Default")
      (node (ref "R357") (pin "1") (pinfunction "1_1") (pintype "passive"))
    )
    (net (code "50") (name "SOM_USB_N") (class "Default")
      (node (ref "R345") (pin "1") (pinfunction "1_1") (pintype "passive"))
    )
    (net (code "51") (name "SOM_USB_P") (class "Default")
      (node (ref "R346") (pin "1") (pinfunction "1_1") (pintype "passive"))
    )
    (net (code "52") (name "USB1_N") (class "Default")
      (node (ref "R341") (pin "1") (pinfunction "1_1") (pintype "passive"))
    )
    (net (code "53") (name "USB1_P") (class "Default")
      (node (ref "R342") (pin "1") (pinfunction "1_1") (pintype "passive"))
    )
    (net (code "54") (name "VDDANA") (class "Default")
      (node (ref "C253") (pin "2") (pinfunction "2_2") (pintype "passive"))
      (node (ref "C275") (pin "1") (pinfunction "1_1") (pintype "passive"))
      (node (ref "C276") (pin "1") (pinfunction "1_1") (pintype "passive"))
      (node (ref "C277") (pin "1") (pinfunction "1_1") (pintype "passive"))
      (node (ref "C283") (pin "1") (pinfunction "1_1") (pintype "passive"))
      (node (ref "C284") (pin "1") (pinfunction "1_1") (pintype "passive"))
      (node (ref "U54") (pin "E5") (pinfunction "VDDANA_E5") (pintype "power_in"))
      (node (ref "U54") (pin "E6") (pinfunction "VDDANA_E6") (pintype "power_in"))
      (node (ref "U54") (pin "G6") (pinfunction "ADVREFP_G6") (pintype "power_in"))
      (node (ref "U54") (pin "J6") (pinfunction "VDDANAOUT_J6") (pintype "power_in"))
      (node (ref "U54") (pin "T15") (pinfunction "VDDDPHY_T15") (pintype "power_in"))
      (node (ref "U54") (pin "T16") (pinfunction "VDDDPHY_T16") (pintype "power_in"))
    )
    (net (code "55") (name "VDDBU") (class "Default")
      (node (ref "C281") (pin "1") (pinfunction "1_1") (pintype "passive"))
      (node (ref "R343") (pin "2") (pinfunction "2_2") (pintype "passive"))
      (node (ref "R364") (pin "2") (pinfunction "2_2") (pintype "passive"))
      (node (ref "R370") (pin "2") (pinfunction "2_2") (pintype "passive"))
      (node (ref "U54") (pin "P11") (pinfunction "VBAT_P11") (pintype "power_in"))
    )
    (net (code "56") (name "VDDCORE") (class "Default")
      (node (ref "C250") (pin "1") (pinfunction "1_1") (pintype "passive"))
      (node (ref "C251") (pin "1") (pinfunction "1_1") (pintype "passive"))
      (node (ref "C252") (pin "1") (pinfunction "1_1") (pintype "passive"))
      (node (ref "C254") (pin "1") (pinfunction "1_1") (pintype "passive"))
      (node (ref "C255") (pin "1") (pinfunction "1_1") (pintype "passive"))
      (node (ref "C256") (pin "1") (pinfunction "1_1") (pintype "passive"))
      (node (ref "C257") (pin "1") (pinfunction "1_1") (pintype "passive"))
      (node (ref "C258") (pin "1") (pinfunction "1_1") (pintype "passive"))
      (node (ref "C259") (pin "1") (pinfunction "1_1") (pintype "passive"))
      (node (ref "C260") (pin "1") (pinfunction "1_1") (pintype "passive"))
      (node (ref "C261") (pin "1") (pinfunction "1_1") (pintype "passive"))
      (node (ref "C262") (pin "1") (pinfunction "1_1") (pintype "passive"))
      (node (ref "C263") (pin "1") (pinfunction "1_1") (pintype "passive"))
      (node (ref "C264") (pin "1") (pinfunction "1_1") (pintype "passive"))
      (node (ref "C265") (pin "1") (pinfunction "1_1") (pintype "passive"))
      (node (ref "C266") (pin "1") (pinfunction "1_1") (pintype "passive"))
      (node (ref "U54") (pin "F15") (pinfunction "VDDCORE_F15") (pintype "power_in"))
      (node (ref "U54") (pin "F6") (pinfunction "VDDCORE_F6") (pintype "power_in"))
      (node (ref "U54") (pin "F9") (pinfunction "VDDCORE_F9") (pintype "power_in"))
      (node (ref "U54") (pin "J13") (pinfunction "VDDCORE_J13") (pintype "power_in"))
      (node (ref "U54") (pin "J9") (pinfunction "VDDCORE_J9") (pintype "power_in"))
      (node (ref "U54") (pin "L19") (pinfunction "VDDCORE_L19") (pintype "power_in"))
      (node (ref "U54") (pin "L3") (pinfunction "VDDCORE_L3") (pintype "power_in"))
      (node (ref "U54") (pin "N13") (pinfunction "VDDCORE_N13") (pintype "power_in"))
      (node (ref "U54") (pin "P19") (pinfunction "VDDCORE_P19") (pintype "power_in"))
      (node (ref "U54") (pin "U16") (pinfunction "VDDCORE_U16") (pintype "power_in"))
      (node (ref "U54") (pin "U17") (pinfunction "VDDCORE_U17") (pintype "power_in"))
      (node (ref "U54") (pin "U19") (pinfunction "VDDCORE_U19") (pintype "power_in"))
      (node (ref "U54") (pin "W17") (pinfunction "VDDCORE_W17") (pintype "power_in"))
      (node (ref "U54") (pin "Y20") (pinfunction "VDDCORE_Y20") (pintype "power_in"))
    )
    (net (code "57") (name "VDDCPU") (class "Default")
      (node (ref "C235") (pin "1") (pinfunction "1_1") (pintype "passive"))
      (node (ref "C236") (pin "1") (pinfunction "1_1") (pintype "passive"))
      (node (ref "C237") (pin "1") (pinfunction "1_1") (pintype "passive"))
      (node (ref "C238") (pin "1") (pinfunction "1_1") (pintype "passive"))
      (node (ref "C239") (pin "1") (pinfunction "1_1") (pintype "passive"))
      (node (ref "C240") (pin "1") (pinfunction "1_1") (pintype "passive"))
      (node (ref "U54") (pin "B20") (pinfunction "VDDCPU_B20") (pintype "power_in"))
      (node (ref "U54") (pin "E16") (pinfunction "VDDCPU_E16") (pintype "power_in"))
      (node (ref "U54") (pin "E17") (pinfunction "VDDCPU_E17") (pintype "power_in"))
      (node (ref "U54") (pin "E19") (pinfunction "VDDCPU_E19") (pintype "power_in"))
      (node (ref "U54") (pin "F16") (pinfunction "VDDCPU_F16") (pintype "power_in"))
    )
    (net (code "58") (name "VDDIN33") (class "Default")
      (node (ref "C279") (pin "1") (pinfunction "1_1") (pintype "passive"))
      (node (ref "C280") (pin "1") (pinfunction "1_1") (pintype "passive"))
      (node (ref "R364") (pin "1") (pinfunction "1_1") (pintype "passive"))
      (node (ref "U54") (pin "H3") (pinfunction "VDDIN33_H3") (pintype "power_in"))
    )
    (net (code "59") (name "VDDUTMII") (class "Default")
      (node (ref "C267") (pin "1") (pinfunction "1_1") (pintype "passive"))
      (node (ref "C268") (pin "1") (pinfunction "1_1") (pintype "passive"))
      (node (ref "C269") (pin "1") (pinfunction "1_1") (pintype "passive"))
      (node (ref "C270") (pin "1") (pinfunction "1_1") (pintype "passive"))
      (node (ref "C272") (pin "1") (pinfunction "1_1") (pintype "passive"))
      (node (ref "C274") (pin "1") (pinfunction "1_1") (pintype "passive"))
      (node (ref "U54") (pin "B2") (pinfunction "VDDUTMI_B2") (pintype "power_in"))
      (node (ref "U54") (pin "C5") (pinfunction "VDDUTMI_C5") (pintype "power_in"))
      (node (ref "U54") (pin "C8") (pinfunction "VDDUTMI_C8") (pintype "power_in"))
      (node (ref "U54") (pin "E3") (pinfunction "VDDUTMI_E3") (pintype "power_in"))
      (node (ref "U54") (pin "F7") (pinfunction "VDDUTMI_F7") (pintype "power_in"))
    )
    (net (code "60") (name "VDD_3V3") (class "Default")
      (node (ref "C273") (pin "2") (pinfunction "2_2") (pintype "passive"))
      (node (ref "C285") (pin "2") (pinfunction "2_2") (pintype "passive"))
      (node (ref "R339") (pin "2") (pinfunction "2_2") (pintype "passive"))
      (node (ref "Y2") (pin "4") (pinfunction "VDD_4") (pintype "power_in"))
      (node (ref "Y4") (pin "1") (pinfunction "~{STB}_1") (pintype "input"))
      (node (ref "Y4") (pin "4") (pinfunction "VDD_4") (pintype "power_in"))
    )
    (net (code "61") (name "VDD_3V3_MPU") (class "Default")
      (node (ref "C241") (pin "1") (pinfunction "1_1") (pintype "passive"))
      (node (ref "C242") (pin "1") (pinfunction "1_1") (pintype "passive"))
      (node (ref "C243") (pin "1") (pinfunction "1_1") (pintype "passive"))
      (node (ref "C244") (pin "1") (pinfunction "1_1") (pintype "passive"))
      (node (ref "C245") (pin "1") (pinfunction "1_1") (pintype "passive"))
      (node (ref "C246") (pin "1") (pinfunction "1_1") (pintype "passive"))
      (node (ref "C247") (pin "1") (pinfunction "1_1") (pintype "passive"))
      (node (ref "C248") (pin "1") (pinfunction "1_1") (pintype "passive"))
      (node (ref "C249") (pin "1") (pinfunction "1_1") (pintype "passive"))
      (node (ref "U54") (pin "C11") (pinfunction "VDDSDMMC1_C11") (pintype "power_in"))
      (node (ref "U54") (pin "C14") (pinfunction "VDDIOP1_C14") (pintype "power_in"))
      (node (ref "U54") (pin "C17") (pinfunction "VDDIOP1_C17") (pintype "power_in"))
      (node (ref "U54") (pin "F13") (pinfunction "VDDSDMMC2_F13") (pintype "power_in"))
      (node (ref "U54") (pin "H19") (pinfunction "VDDQSPI1_H19") (pintype "power_in"))
      (node (ref "U54") (pin "J16") (pinfunction "VDDSDMMC0_J16") (pintype "power_in"))
      (node (ref "U54") (pin "N16") (pinfunction "VDDQSPI0_N16") (pintype "power_in"))
      (node (ref "U54") (pin "T13") (pinfunction "VDDIOP0_T13") (pintype "power_in"))
      (node (ref "U54") (pin "W14") (pinfunction "VDDIOP0_W14") (pintype "power_in"))
    )
    (net (code "62") (name "WKUP") (class "Default")
      (node (ref "U54") (pin "AA15") (pinfunction "WKUP0_AA15") (pintype "input"))
    )
    (net (code "63") (name "unconnected-(U54G-AUDIOCLK-PadK7)") (class "Default")
      (node (ref "U54") (pin "K7") (pinfunction "AUDIOCLK_K7") (pintype "output+no_connect"))
    )
    (net (code "64") (name "unconnected-(U54G-HHSA_CC1-PadD7)") (class "Default")
      (node (ref "U54") (pin "D7") (pinfunction "HHSA_CC1_D7") (pintype "bidirectional+no_connect"))
    )
    (net (code "65") (name "unconnected-(U54G-HHSA_CC2-PadG9)") (class "Default")
      (node (ref "U54") (pin "G9") (pinfunction "HHSA_CC2_G9") (pintype "bidirectional+no_connect"))
    )
    (net (code "66") (name "unconnected-(U54G-HHSB_CC1-PadC7)") (class "Default")
      (node (ref "U54") (pin "C7") (pinfunction "HHSB_CC1_C7") (pintype "bidirectional+no_connect"))
    )
    (net (code "67") (name "unconnected-(U54G-HHSB_CC2-PadE8)") (class "Default")
      (node (ref "U54") (pin "E8") (pinfunction "HHSB_CC2_E8") (pintype "bidirectional+no_connect"))
    )
  )
)
